# 26_-_PWR_PMIC.net
KiCad netlist of a schematic drawn in Altium Designer
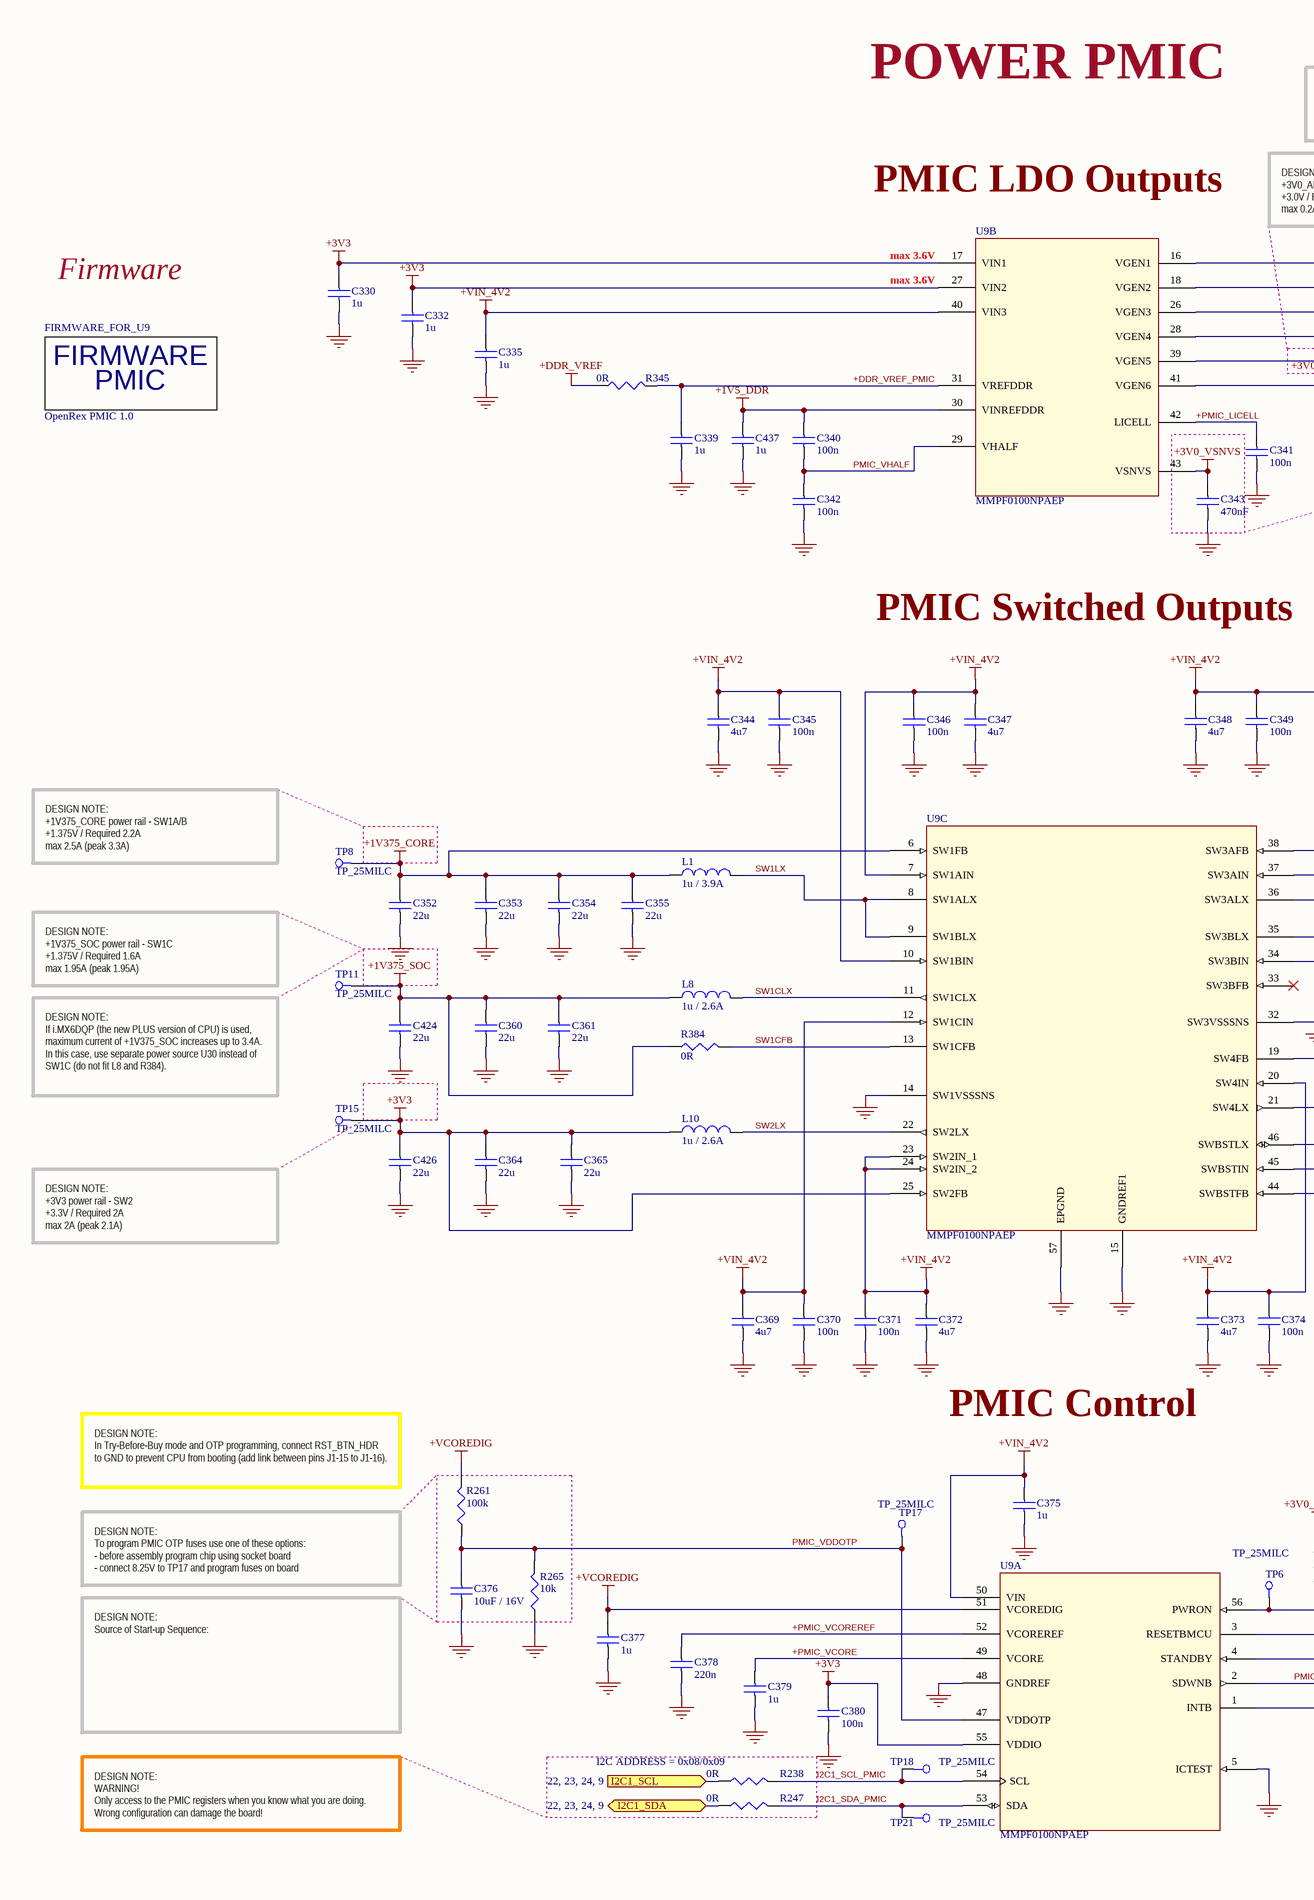
[diagram p0: [26] - PWR PMIC.SchDoc, left]
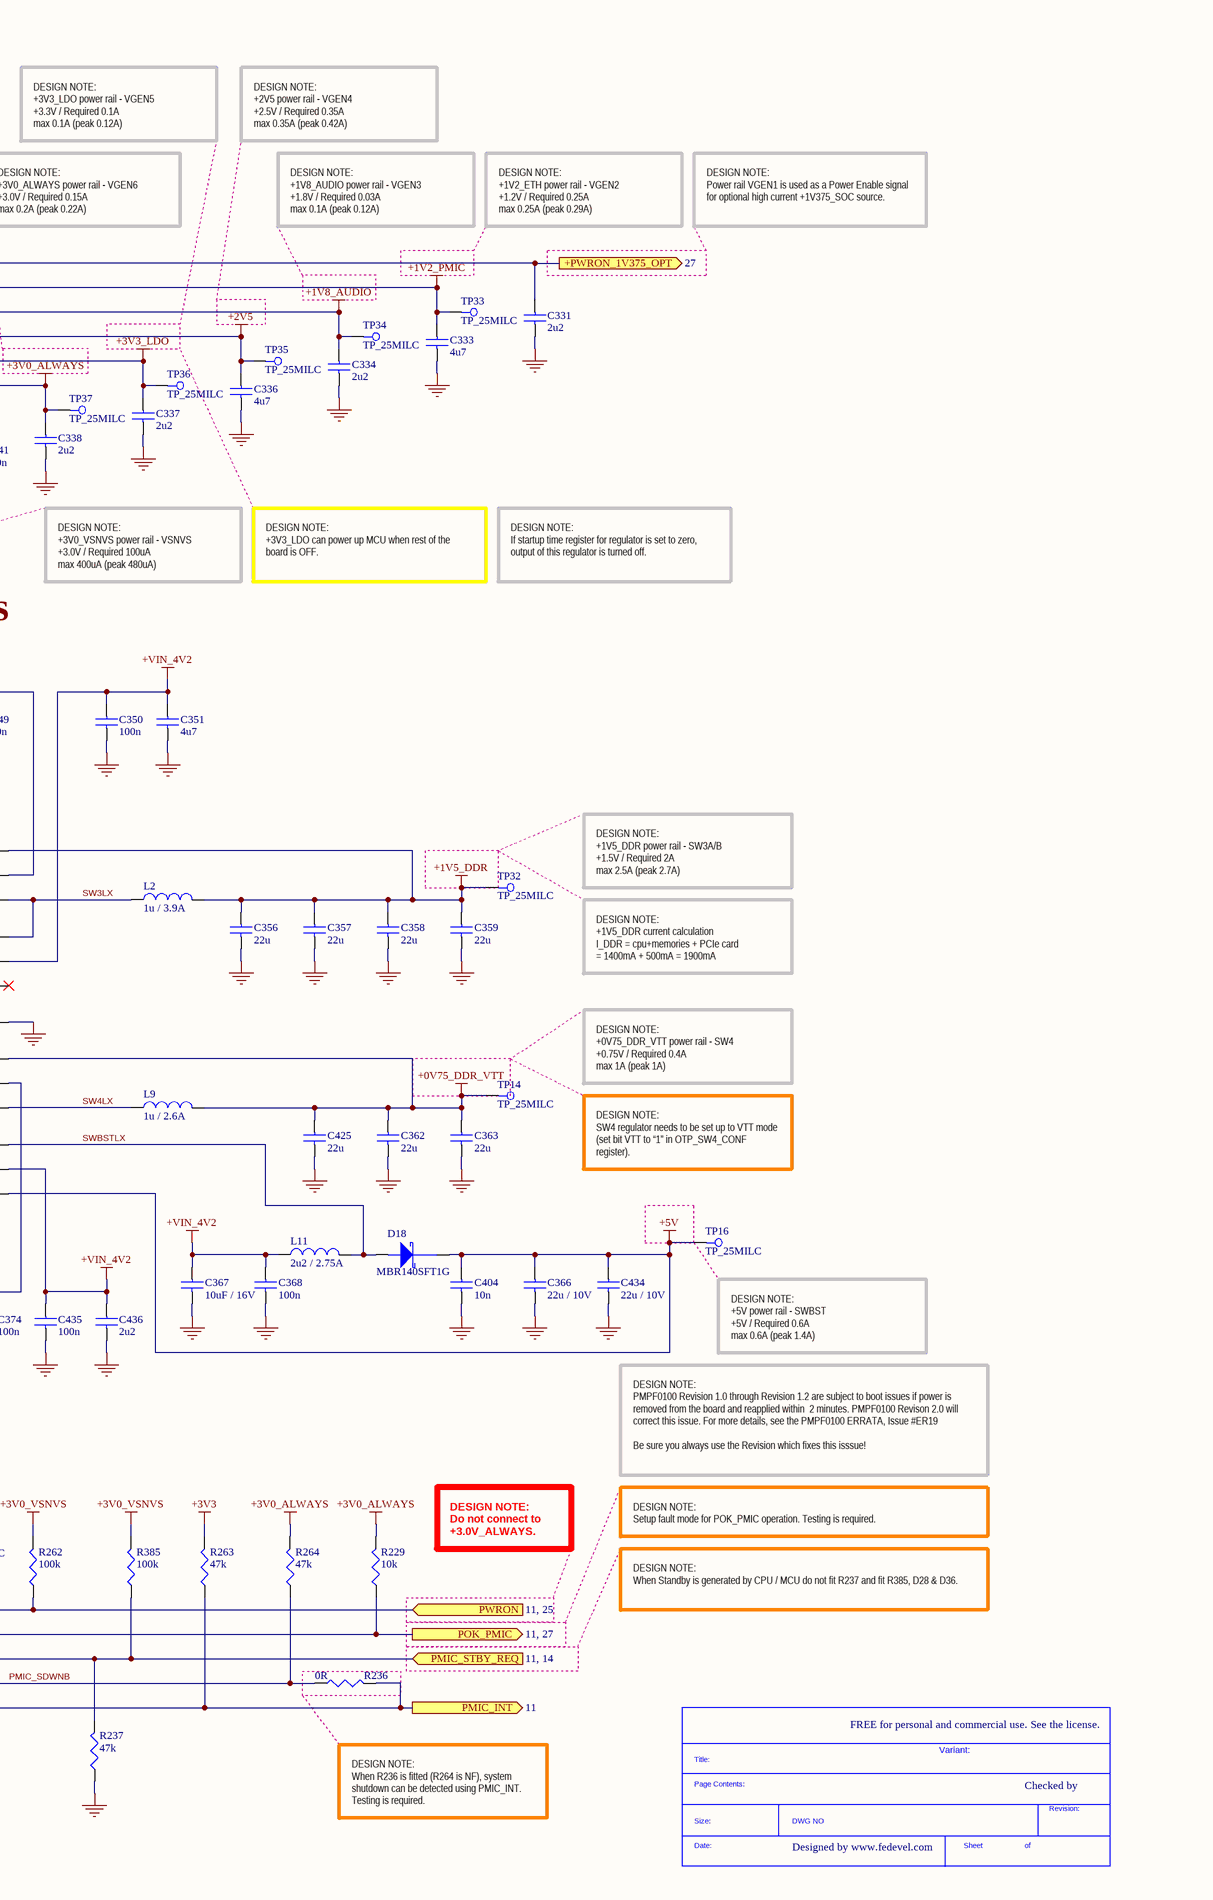
[diagram p1: [26] - PWR PMIC.SchDoc, right]

(export (version "E")
  (design (tool "Eeschema 10.0.6"))
  (components
    (comp (ref "C330")
      (value "1u")
      (footprint "C0402")
      (description "CAP CER 1.0UF 16V X5R 0402")
      (fields
        (field (name "MANUFACTURER") "TDK Corporation")
        (field (name "MANUFACTURER PART NUMBER") "C1005X5R1C105K")
      )
      (libsource (lib "Integrated_Library_FEDEVEL_APR_2015") (part "C1005X5R1C105K"))
    )
    (comp (ref "C331")
      (value "2u2")
      (footprint "C0402")
      (description "CAP CER 2.2UF 10V 10% X5R 0402")
      (fields
        (field (name "MANUFACTURER") "TDK Corporation")
        (field (name "MANUFACTURER PART NUMBER") "C1005X5R1A225K")
      )
      (libsource (lib "Integrated_Library_FEDEVEL_APR_2015") (part "C1005X5R1A225K"))
    )
    (comp (ref "C332")
      (value "1u")
      (footprint "C0402")
      (description "CAP CER 1.0UF 16V X5R 0402")
      (fields
        (field (name "MANUFACTURER") "TDK Corporation")
        (field (name "MANUFACTURER PART NUMBER") "C1005X5R1C105K")
      )
      (libsource (lib "Integrated_Library_FEDEVEL_APR_2015") (part "C1005X5R1C105K"))
    )
    (comp (ref "C333")
      (value "4u7")
      (footprint "C0402")
      (description "CAP CER 4.7UF 10V 20% X5R 0402")
      (fields
        (field (name "MANUFACTURER") "TDK Corporation")
        (field (name "MANUFACTURER PART NUMBER") "C1005X5R1A475M")
      )
      (libsource (lib "Integrated_Library_FEDEVEL_APR_2015") (part "C1005X5R1A475M"))
    )
    (comp (ref "C334")
      (value "2u2")
      (footprint "C0402")
      (description "CAP CER 2.2UF 10V 10% X5R 0402")
      (fields
        (field (name "MANUFACTURER") "TDK Corporation")
        (field (name "MANUFACTURER PART NUMBER") "C1005X5R1A225K")
      )
      (libsource (lib "Integrated_Library_FEDEVEL_APR_2015") (part "C1005X5R1A225K"))
    )
    (comp (ref "C335")
      (value "1u")
      (footprint "C0402")
      (description "CAP CER 1.0UF 16V X5R 0402")
      (fields
        (field (name "MANUFACTURER") "TDK Corporation")
        (field (name "MANUFACTURER PART NUMBER") "C1005X5R1C105K")
      )
      (libsource (lib "Integrated_Library_FEDEVEL_APR_2015") (part "C1005X5R1C105K"))
    )
    (comp (ref "C336")
      (value "4u7")
      (footprint "C0402")
      (description "CAP CER 4.7UF 10V 20% X5R 0402")
      (fields
        (field (name "MANUFACTURER") "TDK Corporation")
        (field (name "MANUFACTURER PART NUMBER") "C1005X5R1A475M")
      )
      (libsource (lib "Integrated_Library_FEDEVEL_APR_2015") (part "C1005X5R1A475M"))
    )
    (comp (ref "C337")
      (value "2u2")
      (footprint "C0402")
      (description "CAP CER 2.2UF 10V 10% X5R 0402")
      (fields
        (field (name "MANUFACTURER") "TDK Corporation")
        (field (name "MANUFACTURER PART NUMBER") "C1005X5R1A225K")
      )
      (libsource (lib "Integrated_Library_FEDEVEL_APR_2015") (part "C1005X5R1A225K"))
    )
    (comp (ref "C338")
      (value "2u2")
      (footprint "C0402")
      (description "CAP CER 2.2UF 10V 10% X5R 0402")
      (fields
        (field (name "MANUFACTURER") "TDK Corporation")
        (field (name "MANUFACTURER PART NUMBER") "C1005X5R1A225K")
      )
      (libsource (lib "Integrated_Library_FEDEVEL_APR_2015") (part "C1005X5R1A225K"))
    )
    (comp (ref "C339")
      (value "1u")
      (footprint "C0402")
      (description "CAP CER 1.0UF 16V X5R 0402")
      (fields
        (field (name "MANUFACTURER") "TDK Corporation")
        (field (name "MANUFACTURER PART NUMBER") "C1005X5R1C105K")
      )
      (libsource (lib "Integrated_Library_FEDEVEL_APR_2015") (part "C1005X5R1C105K"))
    )
    (comp (ref "C340")
      (value "100n")
      (footprint "C0402")
      (description "CAP CER .10UF 50V X5R 10% 0402")
      (fields
        (field (name "MANUFACTURER") "TDK Corporation")
        (field (name "MANUFACTURER PART NUMBER") "C1005X5R1H104K")
      )
      (libsource (lib "Integrated_Library_FEDEVEL_APR_2015") (part "C1005X5R1H104K"))
    )
    (comp (ref "C341")
      (value "100n")
      (footprint "C0402")
      (description "CAP CER .10UF 50V X5R 10% 0402")
      (fields
        (field (name "MANUFACTURER") "TDK Corporation")
        (field (name "MANUFACTURER PART NUMBER") "C1005X5R1H104K")
      )
      (libsource (lib "Integrated_Library_FEDEVEL_APR_2015") (part "C1005X5R1H104K"))
    )
    (comp (ref "C342")
      (value "100n")
      (footprint "C0402")
      (description "CAP CER .10UF 50V X5R 10% 0402")
      (fields
        (field (name "MANUFACTURER") "TDK Corporation")
        (field (name "MANUFACTURER PART NUMBER") "C1005X5R1H104K")
      )
      (libsource (lib "Integrated_Library_FEDEVEL_APR_2015") (part "C1005X5R1H104K"))
    )
    (comp (ref "C343")
      (value "470nF")
      (footprint "C0402")
      (description "CAP CER .47UF 16V X5R 0402")
      (fields
        (field (name "MANUFACTURER") "TDK Corporation")
        (field (name "MANUFACTURER PART NUMBER") "C1005X5R1C474K")
      )
      (libsource (lib "Integrated_Library_FEDEVEL_APR_2015") (part "C1005X5R1C474K"))
    )
    (comp (ref "C344")
      (value "4u7")
      (footprint "C0402")
      (description "CAP CER 4.7UF 10V 20% X5R 0402")
      (fields
        (field (name "MANUFACTURER") "TDK Corporation")
        (field (name "MANUFACTURER PART NUMBER") "C1005X5R1A475M")
      )
      (libsource (lib "Integrated_Library_FEDEVEL_APR_2015") (part "C1005X5R1A475M"))
    )
    (comp (ref "C345")
      (value "100n")
      (footprint "C0402")
      (description "CAP CER .10UF 50V X5R 10% 0402")
      (fields
        (field (name "MANUFACTURER") "TDK Corporation")
        (field (name "MANUFACTURER PART NUMBER") "C1005X5R1H104K")
      )
      (libsource (lib "Integrated_Library_FEDEVEL_APR_2015") (part "C1005X5R1H104K"))
    )
    (comp (ref "C346")
      (value "100n")
      (footprint "C0402")
      (description "CAP CER .10UF 50V X5R 10% 0402")
      (fields
        (field (name "MANUFACTURER") "TDK Corporation")
        (field (name "MANUFACTURER PART NUMBER") "C1005X5R1H104K")
      )
      (libsource (lib "Integrated_Library_FEDEVEL_APR_2015") (part "C1005X5R1H104K"))
    )
    (comp (ref "C347")
      (value "4u7")
      (footprint "C0402")
      (description "CAP CER 4.7UF 10V 20% X5R 0402")
      (fields
        (field (name "MANUFACTURER") "TDK Corporation")
        (field (name "MANUFACTURER PART NUMBER") "C1005X5R1A475M")
      )
      (libsource (lib "Integrated_Library_FEDEVEL_APR_2015") (part "C1005X5R1A475M"))
    )
    (comp (ref "C348")
      (value "4u7")
      (footprint "C0402")
      (description "CAP CER 4.7UF 10V 20% X5R 0402")
      (fields
        (field (name "MANUFACTURER") "TDK Corporation")
        (field (name "MANUFACTURER PART NUMBER") "C1005X5R1A475M")
      )
      (libsource (lib "Integrated_Library_FEDEVEL_APR_2015") (part "C1005X5R1A475M"))
    )
    (comp (ref "C349")
      (value "100n")
      (footprint "C0402")
      (description "CAP CER .10UF 50V X5R 10% 0402")
      (fields
        (field (name "MANUFACTURER") "TDK Corporation")
        (field (name "MANUFACTURER PART NUMBER") "C1005X5R1H104K")
      )
      (libsource (lib "Integrated_Library_FEDEVEL_APR_2015") (part "C1005X5R1H104K"))
    )
    (comp (ref "C350")
      (value "100n")
      (footprint "C0402")
      (description "CAP CER .10UF 50V X5R 10% 0402")
      (fields
        (field (name "MANUFACTURER") "TDK Corporation")
        (field (name "MANUFACTURER PART NUMBER") "C1005X5R1H104K")
      )
      (libsource (lib "Integrated_Library_FEDEVEL_APR_2015") (part "C1005X5R1H104K"))
    )
    (comp (ref "C351")
      (value "4u7")
      (footprint "C0402")
      (description "CAP CER 4.7UF 10V 20% X5R 0402")
      (fields
        (field (name "MANUFACTURER") "TDK Corporation")
        (field (name "MANUFACTURER PART NUMBER") "C1005X5R1A475M")
      )
      (libsource (lib "Integrated_Library_FEDEVEL_APR_2015") (part "C1005X5R1A475M"))
    )
    (comp (ref "C352")
      (value "22u")
      (footprint "C0603")
      (description "CAP CER 22UF 4V 20% X5R 0603")
      (fields
        (field (name "MANUFACTURER") "Murata Electronics North America")
        (field (name "MANUFACTURER PART NUMBER") "GRM188R60G226MEA0L")
      )
      (libsource (lib "Integrated_Library_FEDEVEL_APR_2015") (part "GRM188R60G226MEA0L"))
    )
    (comp (ref "C353")
      (value "22u")
      (footprint "C0603")
      (description "CAP CER 22UF 4V 20% X5R 0603")
      (fields
        (field (name "MANUFACTURER") "Murata Electronics North America")
        (field (name "MANUFACTURER PART NUMBER") "GRM188R60G226MEA0L")
      )
      (libsource (lib "Integrated_Library_FEDEVEL_APR_2015") (part "GRM188R60G226MEA0L"))
    )
    (comp (ref "C354")
      (value "22u")
      (footprint "C0603")
      (description "CAP CER 22UF 4V 20% X5R 0603")
      (fields
        (field (name "MANUFACTURER") "Murata Electronics North America")
        (field (name "MANUFACTURER PART NUMBER") "GRM188R60G226MEA0L")
      )
      (libsource (lib "Integrated_Library_FEDEVEL_APR_2015") (part "GRM188R60G226MEA0L"))
    )
    (comp (ref "C355")
      (value "22u")
      (footprint "C0603")
      (description "CAP CER 22UF 4V 20% X5R 0603")
      (fields
        (field (name "MANUFACTURER") "Murata Electronics North America")
        (field (name "MANUFACTURER PART NUMBER") "GRM188R60G226MEA0L")
      )
      (libsource (lib "Integrated_Library_FEDEVEL_APR_2015") (part "GRM188R60G226MEA0L"))
    )
    (comp (ref "C356")
      (value "22u")
      (footprint "C0603")
      (description "CAP CER 22UF 4V 20% X5R 0603")
      (fields
        (field (name "MANUFACTURER") "Murata Electronics North America")
        (field (name "MANUFACTURER PART NUMBER") "GRM188R60G226MEA0L")
      )
      (libsource (lib "Integrated_Library_FEDEVEL_APR_2015") (part "GRM188R60G226MEA0L"))
    )
    (comp (ref "C357")
      (value "22u")
      (footprint "C0603")
      (description "CAP CER 22UF 4V 20% X5R 0603")
      (fields
        (field (name "MANUFACTURER") "Murata Electronics North America")
        (field (name "MANUFACTURER PART NUMBER") "GRM188R60G226MEA0L")
      )
      (libsource (lib "Integrated_Library_FEDEVEL_APR_2015") (part "GRM188R60G226MEA0L"))
    )
    (comp (ref "C358")
      (value "22u")
      (footprint "C0603")
      (description "CAP CER 22UF 4V 20% X5R 0603")
      (fields
        (field (name "MANUFACTURER") "Murata Electronics North America")
        (field (name "MANUFACTURER PART NUMBER") "GRM188R60G226MEA0L")
      )
      (libsource (lib "Integrated_Library_FEDEVEL_APR_2015") (part "GRM188R60G226MEA0L"))
    )
    (comp (ref "C359")
      (value "22u")
      (footprint "C0603")
      (description "CAP CER 22UF 4V 20% X5R 0603")
      (fields
        (field (name "MANUFACTURER") "Murata Electronics North America")
        (field (name "MANUFACTURER PART NUMBER") "GRM188R60G226MEA0L")
      )
      (libsource (lib "Integrated_Library_FEDEVEL_APR_2015") (part "GRM188R60G226MEA0L"))
    )
    (comp (ref "C360")
      (value "22u")
      (footprint "C0603")
      (description "CAP CER 22UF 4V 20% X5R 0603")
      (fields
        (field (name "MANUFACTURER") "Murata Electronics North America")
        (field (name "MANUFACTURER PART NUMBER") "GRM188R60G226MEA0L")
      )
      (libsource (lib "Integrated_Library_FEDEVEL_APR_2015") (part "GRM188R60G226MEA0L"))
    )
    (comp (ref "C361")
      (value "22u")
      (footprint "C0603")
      (description "CAP CER 22UF 4V 20% X5R 0603")
      (fields
        (field (name "MANUFACTURER") "Murata Electronics North America")
        (field (name "MANUFACTURER PART NUMBER") "GRM188R60G226MEA0L")
      )
      (libsource (lib "Integrated_Library_FEDEVEL_APR_2015") (part "GRM188R60G226MEA0L"))
    )
    (comp (ref "C362")
      (value "22u")
      (footprint "C0603")
      (description "CAP CER 22UF 4V 20% X5R 0603")
      (fields
        (field (name "MANUFACTURER") "Murata Electronics North America")
        (field (name "MANUFACTURER PART NUMBER") "GRM188R60G226MEA0L")
      )
      (libsource (lib "Integrated_Library_FEDEVEL_APR_2015") (part "GRM188R60G226MEA0L"))
    )
    (comp (ref "C363")
      (value "22u")
      (footprint "C0603")
      (description "CAP CER 22UF 4V 20% X5R 0603")
      (fields
        (field (name "MANUFACTURER") "Murata Electronics North America")
        (field (name "MANUFACTURER PART NUMBER") "GRM188R60G226MEA0L")
      )
      (libsource (lib "Integrated_Library_FEDEVEL_APR_2015") (part "GRM188R60G226MEA0L"))
    )
    (comp (ref "C364")
      (value "22u")
      (footprint "C0603")
      (description "CAP CER 22UF 6.3V 20% X5R 0603")
      (fields
        (field (name "MANUFACTURER") "TDK Corporation")
        (field (name "MANUFACTURER PART NUMBER") "C1608X5R0J226M080AC")
      )
      (libsource (lib "Integrated_Library_FEDEVEL_APR_2015") (part "C1608X5R0J226M080AC"))
    )
    (comp (ref "C365")
      (value "22u")
      (footprint "C0603")
      (description "CAP CER 22UF 6.3V 20% X5R 0603")
      (fields
        (field (name "MANUFACTURER") "TDK Corporation")
        (field (name "MANUFACTURER PART NUMBER") "C1608X5R0J226M080AC")
      )
      (libsource (lib "Integrated_Library_FEDEVEL_APR_2015") (part "C1608X5R0J226M080AC"))
    )
    (comp (ref "C366")
      (value "22u / 10V")
      (footprint "C0603")
      (description "CAP CER 22UF 10V X5R 0603")
      (fields
        (field (name "MANUFACTURER") "TDK Corporation")
        (field (name "MANUFACTURER PART NUMBER") "C1608X5R1A226M080AC")
      )
      (libsource (lib "Integrated_Library_FEDEVEL_APR_2015") (part "C1608X5R1A226M080AC"))
    )
    (comp (ref "C367")
      (value "10uF / 16V")
      (footprint "C0805")
      (description "CAP CER 10UF 16V 20% X5R 0805")
      (fields
        (field (name "MANUFACTURER") "TDK Corporation")
        (field (name "MANUFACTURER PART NUMBER") "C2012X5R1C106M/1.25")
      )
      (libsource (lib "Integrated_Library_FEDEVEL_APR_2015") (part "C2012X5R1C106M"))
    )
    (comp (ref "C368")
      (value "100n")
      (footprint "C0402")
      (description "CAP CER .10UF 50V X5R 10% 0402")
      (fields
        (field (name "MANUFACTURER") "TDK Corporation")
        (field (name "MANUFACTURER PART NUMBER") "C1005X5R1H104K")
      )
      (libsource (lib "Integrated_Library_FEDEVEL_APR_2015") (part "C1005X5R1H104K"))
    )
    (comp (ref "C369")
      (value "4u7")
      (footprint "C0402")
      (description "CAP CER 4.7UF 10V 20% X5R 0402")
      (fields
        (field (name "MANUFACTURER") "TDK Corporation")
        (field (name "MANUFACTURER PART NUMBER") "C1005X5R1A475M")
      )
      (libsource (lib "Integrated_Library_FEDEVEL_APR_2015") (part "C1005X5R1A475M"))
    )
    (comp (ref "C370")
      (value "100n")
      (footprint "C0402")
      (description "CAP CER .10UF 50V X5R 10% 0402")
      (fields
        (field (name "MANUFACTURER") "TDK Corporation")
        (field (name "MANUFACTURER PART NUMBER") "C1005X5R1H104K")
      )
      (libsource (lib "Integrated_Library_FEDEVEL_APR_2015") (part "C1005X5R1H104K"))
    )
    (comp (ref "C371")
      (value "100n")
      (footprint "C0402")
      (description "CAP CER .10UF 50V X5R 10% 0402")
      (fields
        (field (name "MANUFACTURER") "TDK Corporation")
        (field (name "MANUFACTURER PART NUMBER") "C1005X5R1H104K")
      )
      (libsource (lib "Integrated_Library_FEDEVEL_APR_2015") (part "C1005X5R1H104K"))
    )
    (comp (ref "C372")
      (value "4u7")
      (footprint "C0402")
      (description "CAP CER 4.7UF 10V 20% X5R 0402")
      (fields
        (field (name "MANUFACTURER") "TDK Corporation")
        (field (name "MANUFACTURER PART NUMBER") "C1005X5R1A475M")
      )
      (libsource (lib "Integrated_Library_FEDEVEL_APR_2015") (part "C1005X5R1A475M"))
    )
    (comp (ref "C373")
      (value "4u7")
      (footprint "C0402")
      (description "CAP CER 4.7UF 10V 20% X5R 0402")
      (fields
        (field (name "MANUFACTURER") "TDK Corporation")
        (field (name "MANUFACTURER PART NUMBER") "C1005X5R1A475M")
      )
      (libsource (lib "Integrated_Library_FEDEVEL_APR_2015") (part "C1005X5R1A475M"))
    )
    (comp (ref "C374")
      (value "100n")
      (footprint "C0402")
      (description "CAP CER .10UF 50V X5R 10% 0402")
      (fields
        (field (name "MANUFACTURER") "TDK Corporation")
        (field (name "MANUFACTURER PART NUMBER") "C1005X5R1H104K")
      )
      (libsource (lib "Integrated_Library_FEDEVEL_APR_2015") (part "C1005X5R1H104K"))
    )
    (comp (ref "C375")
      (value "1u")
      (footprint "C0402")
      (description "CAP CER 1.0UF 16V X5R 0402")
      (fields
        (field (name "MANUFACTURER") "TDK Corporation")
        (field (name "MANUFACTURER PART NUMBER") "C1005X5R1C105K")
      )
      (libsource (lib "Integrated_Library_FEDEVEL_APR_2015") (part "C1005X5R1C105K"))
    )
    (comp (ref "C376")
      (value "10uF / 16V")
      (footprint "C0805")
      (description "CAP CER 10UF 16V 20% X5R 0805")
      (fields
        (field (name "MANUFACTURER") "TDK Corporation")
        (field (name "MANUFACTURER PART NUMBER") "C2012X5R1C106M/1.25")
      )
      (libsource (lib "Integrated_Library_FEDEVEL_APR_2015") (part "C2012X5R1C106M"))
    )
    (comp (ref "C377")
      (value "1u")
      (footprint "C0402")
      (description "CAP CER 1.0UF 16V X5R 0402")
      (fields
        (field (name "MANUFACTURER") "TDK Corporation")
        (field (name "MANUFACTURER PART NUMBER") "C1005X5R1C105K")
      )
      (libsource (lib "Integrated_Library_FEDEVEL_APR_2015") (part "C1005X5R1C105K"))
    )
    (comp (ref "C378")
      (value "220n")
      (footprint "C0402")
      (description "CAP CER .22UF 25V X5R 20% 0402")
      (fields
        (field (name "MANUFACTURER") "TDK Corporation")
        (field (name "MANUFACTURER PART NUMBER") "C1005X5R1E224M")
      )
      (libsource (lib "Integrated_Library_FEDEVEL_APR_2015") (part "C1005X5R1E224M"))
    )
    (comp (ref "C379")
      (value "1u")
      (footprint "C0402")
      (description "CAP CER 1.0UF 16V X5R 0402")
      (fields
        (field (name "MANUFACTURER") "TDK Corporation")
        (field (name "MANUFACTURER PART NUMBER") "C1005X5R1C105K")
      )
      (libsource (lib "Integrated_Library_FEDEVEL_APR_2015") (part "C1005X5R1C105K"))
    )
    (comp (ref "C380")
      (value "100n")
      (footprint "C0402")
      (description "CAP CER .10UF 50V X5R 10% 0402")
      (fields
        (field (name "MANUFACTURER") "TDK Corporation")
        (field (name "MANUFACTURER PART NUMBER") "C1005X5R1H104K")
      )
      (libsource (lib "Integrated_Library_FEDEVEL_APR_2015") (part "C1005X5R1H104K"))
    )
    (comp (ref "C404")
      (value "10n")
      (footprint "C0402")
      (description "CAP CER 10000PF 50V 10% X7R 0402")
      (fields
        (field (name "MANUFACTURER") "TDK Corporation")
        (field (name "MANUFACTURER PART NUMBER") "C1005X7R1H103K")
      )
      (libsource (lib "Integrated_Library_FEDEVEL_APR_2015") (part "C1005X7R1H103K"))
    )
    (comp (ref "C424")
      (value "22u")
      (footprint "C0603")
      (description "CAP CER 22UF 4V 20% X5R 0603")
      (fields
        (field (name "MANUFACTURER") "Murata Electronics North America")
        (field (name "MANUFACTURER PART NUMBER") "GRM188R60G226MEA0L")
      )
      (libsource (lib "Integrated_Library_FEDEVEL_APR_2015") (part "GRM188R60G226MEA0L"))
    )
    (comp (ref "C425")
      (value "22u")
      (footprint "C0603")
      (description "CAP CER 22UF 4V 20% X5R 0603")
      (fields
        (field (name "MANUFACTURER") "Murata Electronics North America")
        (field (name "MANUFACTURER PART NUMBER") "GRM188R60G226MEA0L")
      )
      (libsource (lib "Integrated_Library_FEDEVEL_APR_2015") (part "GRM188R60G226MEA0L"))
    )
    (comp (ref "C426")
      (value "22u")
      (footprint "C0603")
      (description "CAP CER 22UF 6.3V 20% X5R 0603")
      (fields
        (field (name "MANUFACTURER") "TDK Corporation")
        (field (name "MANUFACTURER PART NUMBER") "C1608X5R0J226M080AC")
      )
      (libsource (lib "Integrated_Library_FEDEVEL_APR_2015") (part "C1608X5R0J226M080AC"))
    )
    (comp (ref "C434")
      (value "22u / 10V")
      (footprint "C0603")
      (description "CAP CER 22UF 10V X5R 0603")
      (fields
        (field (name "MANUFACTURER") "TDK Corporation")
        (field (name "MANUFACTURER PART NUMBER") "C1608X5R1A226M080AC")
      )
      (libsource (lib "Integrated_Library_FEDEVEL_APR_2015") (part "C1608X5R1A226M080AC"))
    )
    (comp (ref "C435")
      (value "100n")
      (footprint "C0402")
      (description "CAP CER .10UF 50V X5R 10% 0402")
      (fields
        (field (name "MANUFACTURER") "TDK Corporation")
        (field (name "MANUFACTURER PART NUMBER") "C1005X5R1H104K")
      )
      (libsource (lib "Integrated_Library_FEDEVEL_APR_2015") (part "C1005X5R1H104K"))
    )
    (comp (ref "C436")
      (value "2u2")
      (footprint "C0402")
      (description "CAP CER 2.2UF 10V 10% X5R 0402")
      (fields
        (field (name "MANUFACTURER") "TDK Corporation")
        (field (name "MANUFACTURER PART NUMBER") "C1005X5R1A225K")
      )
      (libsource (lib "Integrated_Library_FEDEVEL_APR_2015") (part "C1005X5R1A225K"))
    )
    (comp (ref "C437")
      (value "1u")
      (footprint "C0402")
      (description "CAP CER 1.0UF 16V X5R 0402")
      (fields
        (field (name "MANUFACTURER") "TDK Corporation")
        (field (name "MANUFACTURER PART NUMBER") "C1005X5R1C105K")
      )
      (libsource (lib "Integrated_Library_FEDEVEL_APR_2015") (part "C1005X5R1C105K"))
    )
    (comp (ref "D18")
      (value "MBR140SFT1G")
      (footprint "SOD-123FL")
      (description "DIODE SCHOTTKY 40V 1A SOD123L")
      (fields (field (name "MANUFACTURER") "ON Semiconductor"))
      (libsource (lib "Integrated_Library_FEDEVEL_APR_2015") (part "MBR140SFT1G"))
    )
    (comp (ref "FIRMWARE_FOR_U9")
      (value "OpenRex PMIC 1.0")
      (libsource (lib "Integrated_Library_FEDEVEL_APR_2015") (part "FIRMWARE_OpenRex_PMIC_1.0"))
    )
    (comp (ref "L1")
      (value "1u / 3.9A")
      (footprint "IHLP_118MILX144MIL")
      (description "FIXED IND 1UH 3.9A 33 MOHM SMD")
      (fields
        (field (name "MANUFACTURER") "Vishay Dale")
        (field (name "MANUFACTURER PART NUMBER") "IHLP1212AEER1R0M11")
      )
      (libsource (lib "") (part "IHLP1212AEER1R0M11_1"))
    )
    (comp (ref "L2")
      (value "1u / 3.9A")
      (footprint "IHLP_118MILX144MIL")
      (description "FIXED IND 1UH 3.9A 33 MOHM SMD")
      (fields
        (field (name "MANUFACTURER") "Vishay Dale")
        (field (name "MANUFACTURER PART NUMBER") "IHLP1212AEER1R0M11")
      )
      (libsource (lib "Integrated_Library_FEDEVEL_APR_2015") (part "IHLP1212AEER1R0M11"))
    )
    (comp (ref "L8")
      (value "1u / 2.6A")
      (footprint "IFSC_79MILX98MIL")
      (description "FIXED IND 1UH 2.6A 43 MOHM SMD")
      (fields
        (field (name "MANUFACTURER") "Vishay Dale")
        (field (name "MANUFACTURER PART NUMBER") "IFSC1008ABER1R0M01")
      )
      (libsource (lib "Integrated_Library_FEDEVEL_APR_2015") (part "IFSC1008ABER1R0M01"))
    )
    (comp (ref "L9")
      (value "1u / 2.6A")
      (footprint "IFSC_79MILX98MIL")
      (description "FIXED IND 1UH 2.6A 43 MOHM SMD")
      (fields
        (field (name "MANUFACTURER") "Vishay Dale")
        (field (name "MANUFACTURER PART NUMBER") "IFSC1008ABER1R0M01")
      )
      (libsource (lib "Integrated_Library_FEDEVEL_APR_2015") (part "IFSC1008ABER1R0M01"))
    )
    (comp (ref "L10")
      (value "1u / 2.6A")
      (footprint "IFSC_79MILX98MIL")
      (description "FIXED IND 1UH 2.6A 43 MOHM SMD")
      (fields
        (field (name "MANUFACTURER") "Vishay Dale")
        (field (name "MANUFACTURER PART NUMBER") "IFSC1008ABER1R0M01")
      )
      (libsource (lib "") (part "IFSC1008ABER1R0M01_1"))
    )
    (comp (ref "L11")
      (value "2u2 / 2.75A")
      (footprint "IHLP_160MILX175MIL")
      (description "FIXED IND 2.2UH 2.75A 83.5 MOHM")
      (fields
        (field (name "MANUFACTURER") "Vishay Dale")
        (field (name "MANUFACTURER PART NUMBER") "IHLP1616ABER2R2M11")
      )
      (libsource (lib "Integrated_Library_FEDEVEL_APR_2015") (part "IHLP1616ABER2R2M11"))
    )
    (comp (ref "R229")
      (value "10k")
      (footprint "R0402")
      (description "RES 10.0K OHM 1/16W 1% 0402 SMD")
      (fields
        (field (name "MANUFACTURER") "Yageo")
        (field (name "MANUFACTURER PART NUMBER") "RC0402FR-0710KL")
      )
      (libsource (lib "Integrated_Library_FEDEVEL_APR_2015") (part "RC0402FR-0710KL"))
    )
    (comp (ref "R236")
      (value "0R")
      (footprint "R0402")
      (description "RES 0.0 OHM 1/16W 0402 SMD")
      (fields
        (field (name "MANUFACTURER") "Yageo")
        (field (name "MANUFACTURER PART NUMBER") "RC0402JR-070RL")
      )
      (libsource (lib "Integrated_Library_FEDEVEL_APR_2015") (part "RC0402JR-070RL"))
    )
    (comp (ref "R237")
      (value "47k")
      (footprint "R0402")
      (description "RES 47.0K OHM 1/16W 1% 0402 SMD")
      (fields
        (field (name "MANUFACTURER") "Yageo")
        (field (name "MANUFACTURER PART NUMBER") "RC0402FR-0747KL")
      )
      (libsource (lib "Integrated_Library_FEDEVEL_APR_2015") (part "RC0402FR-0747KL"))
    )
    (comp (ref "R238")
      (value "0R")
      (footprint "R0402")
      (description "RES 0.0 OHM 1/16W 0402 SMD")
      (fields
        (field (name "MANUFACTURER") "Yageo")
        (field (name "MANUFACTURER PART NUMBER") "RC0402JR-070RL")
      )
      (libsource (lib "Integrated_Library_FEDEVEL_APR_2015") (part "RC0402JR-070RL"))
    )
    (comp (ref "R247")
      (value "0R")
      (footprint "R0402")
      (description "RES 0.0 OHM 1/16W 0402 SMD")
      (fields
        (field (name "MANUFACTURER") "Yageo")
        (field (name "MANUFACTURER PART NUMBER") "RC0402JR-070RL")
      )
      (libsource (lib "Integrated_Library_FEDEVEL_APR_2015") (part "RC0402JR-070RL"))
    )
    (comp (ref "R261")
      (value "100k")
      (footprint "R0402")
      (description "RES 100K OHM 1/16W 1% 0402 SMD")
      (fields
        (field (name "MANUFACTURER") "Stackpole Electronics Inc")
        (field (name "MANUFACTURER PART NUMBER") "RMCF0402FT100K")
      )
      (libsource (lib "Integrated_Library_FEDEVEL_APR_2015") (part "RMCF0402FT100K"))
    )
    (comp (ref "R262")
      (value "100k")
      (footprint "R0402")
      (description "RES 100K OHM 1/16W 1% 0402 SMD")
      (fields
        (field (name "MANUFACTURER") "Stackpole Electronics Inc")
        (field (name "MANUFACTURER PART NUMBER") "RMCF0402FT100K")
      )
      (libsource (lib "Integrated_Library_FEDEVEL_APR_2015") (part "RMCF0402FT100K"))
    )
    (comp (ref "R263")
      (value "47k")
      (footprint "R0402")
      (description "RES 47.0K OHM 1/16W 1% 0402 SMD")
      (fields
        (field (name "MANUFACTURER") "Yageo")
        (field (name "MANUFACTURER PART NUMBER") "RC0402FR-0747KL")
      )
      (libsource (lib "Integrated_Library_FEDEVEL_APR_2015") (part "RC0402FR-0747KL"))
    )
    (comp (ref "R264")
      (value "47k")
      (footprint "R0402")
      (description "RES 47.0K OHM 1/16W 1% 0402 SMD")
      (fields
        (field (name "MANUFACTURER") "Yageo")
        (field (name "MANUFACTURER PART NUMBER") "RC0402FR-0747KL")
      )
      (libsource (lib "Integrated_Library_FEDEVEL_APR_2015") (part "RC0402FR-0747KL"))
    )
    (comp (ref "R265")
      (value "10k")
      (footprint "R0402")
      (description "RES 10.0K OHM 1/16W 1% 0402 SMD")
      (fields
        (field (name "MANUFACTURER") "Yageo")
        (field (name "MANUFACTURER PART NUMBER") "RC0402FR-0710KL")
      )
      (libsource (lib "Integrated_Library_FEDEVEL_APR_2015") (part "RC0402FR-0710KL"))
    )
    (comp (ref "R345")
      (value "0R")
      (footprint "R0402")
      (description "RES 0.0 OHM 1/16W 0402 SMD")
      (fields
        (field (name "MANUFACTURER") "Yageo")
        (field (name "MANUFACTURER PART NUMBER") "RC0402JR-070RL")
      )
      (libsource (lib "Integrated_Library_FEDEVEL_APR_2015") (part "RC0402JR-070RL"))
    )
    (comp (ref "R384")
      (value "0R")
      (footprint "R0402")
      (description "RES 0.0 OHM 1/16W 0402 SMD")
      (fields
        (field (name "MANUFACTURER") "Yageo")
        (field (name "MANUFACTURER PART NUMBER") "RC0402JR-070RL")
      )
      (libsource (lib "Integrated_Library_FEDEVEL_APR_2015") (part "RC0402JR-070RL"))
    )
    (comp (ref "R385")
      (value "100k")
      (footprint "R0402")
      (description "RES 100K OHM 1/16W 1% 0402 SMD")
      (fields
        (field (name "MANUFACTURER") "Stackpole Electronics Inc")
        (field (name "MANUFACTURER PART NUMBER") "RMCF0402FT100K")
      )
      (libsource (lib "Integrated_Library_FEDEVEL_APR_2015") (part "RMCF0402FT100K"))
    )
    (comp (ref "TP6")
      (value "TP_25MILC")
      (footprint "TP_25C")
      (description "Test Point 25mil")
      (libsource (lib "Integrated_Library_FEDEVEL_APR_2015") (part "TP_25MILC"))
    )
    (comp (ref "TP8")
      (value "TP_25MILC")
      (footprint "TP_25C")
      (description "Test Point 25mil")
      (libsource (lib "Integrated_Library_FEDEVEL_APR_2015") (part "TP_25MILC"))
    )
    (comp (ref "TP11")
      (value "TP_25MILC")
      (footprint "TP_25C")
      (description "Test Point 25mil")
      (libsource (lib "Integrated_Library_FEDEVEL_APR_2015") (part "TP_25MILC"))
    )
    (comp (ref "TP14")
      (value "TP_25MILC")
      (footprint "TP_25C")
      (description "Test Point 25mil")
      (libsource (lib "Integrated_Library_FEDEVEL_APR_2015") (part "TP_25MILC"))
    )
    (comp (ref "TP15")
      (value "TP_25MILC")
      (footprint "TP_25C")
      (description "Test Point 25mil")
      (libsource (lib "Integrated_Library_FEDEVEL_APR_2015") (part "TP_25MILC"))
    )
    (comp (ref "TP16")
      (value "TP_25MILC")
      (footprint "TP_25C")
      (description "Test Point 25mil")
      (libsource (lib "Integrated_Library_FEDEVEL_APR_2015") (part "TP_25MILC"))
    )
    (comp (ref "TP17")
      (value "TP_25MILC")
      (footprint "TP_25C")
      (description "Test Point 25mil")
      (libsource (lib "Integrated_Library_FEDEVEL_APR_2015") (part "TP_25MILC"))
    )
    (comp (ref "TP18")
      (value "TP_25MILC")
      (footprint "TP_25C")
      (description "Test Point 25mil")
      (libsource (lib "Integrated_Library_FEDEVEL_APR_2015") (part "TP_25MILC"))
    )
    (comp (ref "TP21")
      (value "TP_25MILC")
      (footprint "TP_25C")
      (description "Test Point 25mil")
      (libsource (lib "Integrated_Library_FEDEVEL_APR_2015") (part "TP_25MILC"))
    )
    (comp (ref "TP32")
      (value "TP_25MILC")
      (footprint "TP_25C")
      (description "Test Point 25mil")
      (libsource (lib "Integrated_Library_FEDEVEL_APR_2015") (part "TP_25MILC"))
    )
    (comp (ref "TP33")
      (value "TP_25MILC")
      (footprint "TP_25C")
      (description "Test Point 25mil")
      (libsource (lib "Integrated_Library_FEDEVEL_APR_2015") (part "TP_25MILC"))
    )
    (comp (ref "TP34")
      (value "TP_25MILC")
      (footprint "TP_25C")
      (description "Test Point 25mil")
      (libsource (lib "Integrated_Library_FEDEVEL_APR_2015") (part "TP_25MILC"))
    )
    (comp (ref "TP35")
      (value "TP_25MILC")
      (footprint "TP_25C")
      (description "Test Point 25mil")
      (libsource (lib "Integrated_Library_FEDEVEL_APR_2015") (part "TP_25MILC"))
    )
    (comp (ref "TP36")
      (value "TP_25MILC")
      (footprint "TP_25C")
      (description "Test Point 25mil")
      (libsource (lib "Integrated_Library_FEDEVEL_APR_2015") (part "TP_25MILC"))
    )
    (comp (ref "TP37")
      (value "TP_25MILC")
      (footprint "TP_25C")
      (description "Test Point 25mil")
      (libsource (lib "Integrated_Library_FEDEVEL_APR_2015") (part "TP_25MILC"))
    )
    (comp (ref "U9")
      (value "MMPF0100NPAEP")
      (footprint "56-VFQFN EP")
      (description "IC PWR MGMT I.MX6 56QFN")
      (fields (field (name "MANUFACTURER") "Freescale Semiconductor"))
      (libsource (lib "Integrated_Library_FEDEVEL_APR_2015") (part "MMPF0100NPAEP"))
    )
  )
  (nets
    (net (code "1") (name "+0V75_DDR_VTT") (class "Default")
      (node (ref "C362") (pin "1") (pinfunction "1_1") (pintype "passive"))
      (node (ref "C363") (pin "1") (pinfunction "1_1") (pintype "passive"))
      (node (ref "C425") (pin "1") (pinfunction "1_1") (pintype "passive"))
      (node (ref "L9") (pin "2") (pinfunction "2_2") (pintype "passive"))
      (node (ref "TP14") (pin "1") (pinfunction "1_1") (pintype "passive"))
      (node (ref "U9") (pin "19") (pinfunction "SW4FB_19") (pintype "passive"))
    )
    (net (code "2") (name "+1V2_PMIC") (class "Default")
      (node (ref "C333") (pin "1") (pinfunction "1_1") (pintype "passive"))
      (node (ref "TP33") (pin "1") (pinfunction "1_1") (pintype "passive"))
      (node (ref "U9") (pin "18") (pinfunction "VGEN2_18") (pintype "power_in"))
    )
    (net (code "3") (name "+1V5_DDR") (class "Default")
      (node (ref "C340") (pin "1") (pinfunction "1_1") (pintype "passive"))
      (node (ref "C356") (pin "1") (pinfunction "1_1") (pintype "passive"))
      (node (ref "C357") (pin "1") (pinfunction "1_1") (pintype "passive"))
      (node (ref "C358") (pin "1") (pinfunction "1_1") (pintype "passive"))
      (node (ref "C359") (pin "1") (pinfunction "1_1") (pintype "passive"))
      (node (ref "C437") (pin "1") (pinfunction "1_1") (pintype "passive"))
      (node (ref "L2") (pin "2") (pinfunction "2_2") (pintype "passive"))
      (node (ref "TP32") (pin "1") (pinfunction "1_1") (pintype "passive"))
      (node (ref "U9") (pin "30") (pinfunction "VINREFDDR_30") (pintype "power_in"))
      (node (ref "U9") (pin "38") (pinfunction "SW3AFB_38") (pintype "input"))
    )
    (net (code "4") (name "+1V8_AUDIO") (class "Default")
      (node (ref "C334") (pin "1") (pinfunction "1_1") (pintype "passive"))
      (node (ref "TP34") (pin "1") (pinfunction "1_1") (pintype "passive"))
      (node (ref "U9") (pin "26") (pinfunction "VGEN3_26") (pintype "power_in"))
    )
    (net (code "5") (name "+1V375_CORE") (class "Default")
      (node (ref "C352") (pin "1") (pinfunction "1_1") (pintype "passive"))
      (node (ref "C353") (pin "1") (pinfunction "1_1") (pintype "passive"))
      (node (ref "C354") (pin "1") (pinfunction "1_1") (pintype "passive"))
      (node (ref "C355") (pin "1") (pinfunction "1_1") (pintype "passive"))
      (node (ref "L1") (pin "2") (pinfunction "2_2") (pintype "passive"))
      (node (ref "TP8") (pin "1") (pinfunction "1_1") (pintype "passive"))
      (node (ref "U9") (pin "6") (pinfunction "SW1FB_6") (pintype "input"))
    )
    (net (code "6") (name "+1V375_SOC") (class "Default")
      (node (ref "C360") (pin "1") (pinfunction "1_1") (pintype "passive"))
      (node (ref "C361") (pin "1") (pinfunction "1_1") (pintype "passive"))
      (node (ref "C424") (pin "1") (pinfunction "1_1") (pintype "passive"))
      (node (ref "L8") (pin "1") (pinfunction "1_1") (pintype "passive"))
      (node (ref "R384") (pin "1") (pinfunction "1_1") (pintype "passive"))
      (node (ref "TP11") (pin "1") (pinfunction "1_1") (pintype "passive"))
    )
    (net (code "7") (name "+2V5") (class "Default")
      (node (ref "C336") (pin "1") (pinfunction "1_1") (pintype "passive"))
      (node (ref "TP35") (pin "1") (pinfunction "1_1") (pintype "passive"))
      (node (ref "U9") (pin "28") (pinfunction "VGEN4_28") (pintype "power_in"))
    )
    (net (code "8") (name "+3V0_ALWAYS") (class "Default")
      (node (ref "C338") (pin "1") (pinfunction "1_1") (pintype "passive"))
      (node (ref "R229") (pin "2") (pinfunction "2_2") (pintype "passive"))
      (node (ref "R264") (pin "2") (pinfunction "2_2") (pintype "passive"))
      (node (ref "TP37") (pin "1") (pinfunction "1_1") (pintype "passive"))
      (node (ref "U9") (pin "41") (pinfunction "VGEN6_41") (pintype "power_in"))
    )
    (net (code "9") (name "+3V0_VSNVS") (class "Default")
      (node (ref "C343") (pin "1") (pinfunction "1_1") (pintype "passive"))
      (node (ref "R262") (pin "2") (pinfunction "2_2") (pintype "passive"))
      (node (ref "R385") (pin "2") (pinfunction "2_2") (pintype "passive"))
      (node (ref "U9") (pin "43") (pinfunction "VSNVS_43") (pintype "power_in"))
    )
    (net (code "10") (name "+3V3") (class "Default")
      (node (ref "C330") (pin "1") (pinfunction "1_1") (pintype "passive"))
      (node (ref "C332") (pin "1") (pinfunction "1_1") (pintype "passive"))
      (node (ref "C364") (pin "1") (pinfunction "1_1") (pintype "passive"))
      (node (ref "C365") (pin "1") (pinfunction "1_1") (pintype "passive"))
      (node (ref "C380") (pin "1") (pinfunction "1_1") (pintype "passive"))
      (node (ref "C426") (pin "1") (pinfunction "1_1") (pintype "passive"))
      (node (ref "L10") (pin "2") (pinfunction "2_2") (pintype "passive"))
      (node (ref "R263") (pin "2") (pinfunction "2_2") (pintype "passive"))
      (node (ref "TP15") (pin "1") (pinfunction "1_1") (pintype "passive"))
      (node (ref "U9") (pin "17") (pinfunction "VIN1_17") (pintype "power_in"))
      (node (ref "U9") (pin "25") (pinfunction "SW2FB_25") (pintype "input"))
      (node (ref "U9") (pin "27") (pinfunction "VIN2_27") (pintype "power_in"))
      (node (ref "U9") (pin "55") (pinfunction "VDDIO_55") (pintype "power_in"))
    )
    (net (code "11") (name "+3V3_LDO") (class "Default")
      (node (ref "C337") (pin "1") (pinfunction "1_1") (pintype "passive"))
      (node (ref "TP36") (pin "1") (pinfunction "1_1") (pintype "passive"))
      (node (ref "U9") (pin "39") (pinfunction "VGEN5_39") (pintype "power_in"))
    )
    (net (code "12") (name "+5V") (class "Default")
      (node (ref "C366") (pin "1") (pinfunction "1_1") (pintype "passive"))
      (node (ref "C404") (pin "1") (pinfunction "1_1") (pintype "passive"))
      (node (ref "C434") (pin "1") (pinfunction "1_1") (pintype "passive"))
      (node (ref "D18") (pin "1") (pinfunction "Cathode_1") (pintype "passive"))
      (node (ref "TP16") (pin "1") (pinfunction "1_1") (pintype "passive"))
      (node (ref "U9") (pin "44") (pinfunction "SWBSTFB_44") (pintype "input"))
    )
    (net (code "13") (name "+DDR_VREF") (class "Default")
      (node (ref "R345") (pin "1") (pinfunction "1_1") (pintype "passive"))
    )
    (net (code "14") (name "+VCOREDIG") (class "Default")
      (node (ref "C377") (pin "1") (pinfunction "1_1") (pintype "passive"))
      (node (ref "R261") (pin "2") (pinfunction "2_2") (pintype "passive"))
      (node (ref "U9") (pin "51") (pinfunction "VCOREDIG_51") (pintype "power_in"))
    )
    (net (code "15") (name "+VIN_4V2") (class "Default")
      (node (ref "C335") (pin "1") (pinfunction "1_1") (pintype "passive"))
      (node (ref "C344") (pin "1") (pinfunction "1_1") (pintype "passive"))
      (node (ref "C345") (pin "1") (pinfunction "1_1") (pintype "passive"))
      (node (ref "C346") (pin "1") (pinfunction "1_1") (pintype "passive"))
      (node (ref "C347") (pin "1") (pinfunction "1_1") (pintype "passive"))
      (node (ref "C348") (pin "1") (pinfunction "1_1") (pintype "passive"))
      (node (ref "C349") (pin "1") (pinfunction "1_1") (pintype "passive"))
      (node (ref "C350") (pin "1") (pinfunction "1_1") (pintype "passive"))
      (node (ref "C351") (pin "1") (pinfunction "1_1") (pintype "passive"))
      (node (ref "C367") (pin "1") (pinfunction "1_1") (pintype "passive"))
      (node (ref "C368") (pin "1") (pinfunction "1_1") (pintype "passive"))
      (node (ref "C369") (pin "1") (pinfunction "1_1") (pintype "passive"))
      (node (ref "C370") (pin "1") (pinfunction "1_1") (pintype "passive"))
      (node (ref "C371") (pin "1") (pinfunction "1_1") (pintype "passive"))
      (node (ref "C372") (pin "1") (pinfunction "1_1") (pintype "passive"))
      (node (ref "C373") (pin "1") (pinfunction "1_1") (pintype "passive"))
      (node (ref "C374") (pin "1") (pinfunction "1_1") (pintype "passive"))
      (node (ref "C375") (pin "1") (pinfunction "1_1") (pintype "passive"))
      (node (ref "C435") (pin "1") (pinfunction "1_1") (pintype "passive"))
      (node (ref "C436") (pin "1") (pinfunction "1_1") (pintype "passive"))
      (node (ref "L11") (pin "1") (pinfunction "1_1") (pintype "passive"))
      (node (ref "U9") (pin "10") (pinfunction "SW1BIN_10") (pintype "input"))
      (node (ref "U9") (pin "12") (pinfunction "SW1CIN_12") (pintype "input"))
      (node (ref "U9") (pin "20") (pinfunction "SW4IN_20") (pintype "input"))
      (node (ref "U9") (pin "23") (pinfunction "SW2IN_1_23") (pintype "input"))
      (node (ref "U9") (pin "24") (pinfunction "SW2IN_2_24") (pintype "input"))
      (node (ref "U9") (pin "34") (pinfunction "SW3BIN_34") (pintype "input"))
      (node (ref "U9") (pin "37") (pinfunction "SW3AIN_37") (pintype "input"))
      (node (ref "U9") (pin "40") (pinfunction "VIN3_40") (pintype "power_in"))
      (node (ref "U9") (pin "45") (pinfunction "SWBSTIN_45") (pintype "input"))
      (node (ref "U9") (pin "50") (pinfunction "VIN_50") (pintype "power_in"))
      (node (ref "U9") (pin "7") (pinfunction "SW1AIN_7") (pintype "input"))
    )
    (net (code "16") (name "/+DDR_VREF_PMIC") (class "Default")
      (node (ref "C339") (pin "1") (pinfunction "1_1") (pintype "passive"))
      (node (ref "R345") (pin "2") (pinfunction "2_2") (pintype "passive"))
      (node (ref "U9") (pin "31") (pinfunction "VREFDDR_31") (pintype "power_in"))
    )
    (net (code "17") (name "/+PMIC_LICELL") (class "Default")
      (node (ref "C341") (pin "1") (pinfunction "1_1") (pintype "passive"))
      (node (ref "U9") (pin "42") (pinfunction "LICELL_42") (pintype "power_in"))
    )
    (net (code "18") (name "/+PMIC_VCORE") (class "Default")
      (node (ref "C379") (pin "1") (pinfunction "1_1") (pintype "passive"))
      (node (ref "U9") (pin "49") (pinfunction "VCORE_49") (pintype "power_in"))
    )
    (net (code "19") (name "/+PMIC_VCOREREF") (class "Default")
      (node (ref "C378") (pin "1") (pinfunction "1_1") (pintype "passive"))
      (node (ref "U9") (pin "52") (pinfunction "VCOREREF_52") (pintype "power_in"))
    )
    (net (code "20") (name "/+PWRON_1V375_OPT") (class "Default")
      (node (ref "C331") (pin "1") (pinfunction "1_1") (pintype "passive"))
      (node (ref "U9") (pin "16") (pinfunction "VGEN1_16") (pintype "power_in"))
    )
    (net (code "21") (name "/I2C1_SCL") (class "Default")
      (node (ref "R238") (pin "1") (pinfunction "1_1") (pintype "passive"))
    )
    (net (code "22") (name "/I2C1_SCL_PMIC") (class "Default")
      (node (ref "R238") (pin "2") (pinfunction "2_2") (pintype "passive"))
      (node (ref "TP18") (pin "1") (pinfunction "1_1") (pintype "passive"))
      (node (ref "U9") (pin "54") (pinfunction "SCL_54") (pintype "passive"))
    )
    (net (code "23") (name "/I2C1_SDA") (class "Default")
      (node (ref "R247") (pin "1") (pinfunction "1_1") (pintype "passive"))
    )
    (net (code "24") (name "/I2C1_SDA_PMIC") (class "Default")
      (node (ref "R247") (pin "2") (pinfunction "2_2") (pintype "passive"))
      (node (ref "TP21") (pin "1") (pinfunction "1_1") (pintype "passive"))
      (node (ref "U9") (pin "53") (pinfunction "SDA_53") (pintype "bidirectional"))
    )
    (net (code "25") (name "/PMIC_INT") (class "Default")
      (node (ref "R236") (pin "2") (pinfunction "2_2") (pintype "passive"))
      (node (ref "R263") (pin "1") (pinfunction "1_1") (pintype "passive"))
      (node (ref "U9") (pin "1") (pinfunction "INTB_1") (pintype "passive"))
    )
    (net (code "26") (name "/PMIC_SDWNB") (class "Default")
      (node (ref "R236") (pin "1") (pinfunction "1_1") (pintype "passive"))
      (node (ref "R264") (pin "1") (pinfunction "1_1") (pintype "passive"))
      (node (ref "U9") (pin "2") (pinfunction "SDWNB_2") (pintype "output"))
    )
    (net (code "27") (name "/PMIC_STBY_REQ") (class "Default")
      (node (ref "R237") (pin "2") (pinfunction "2_2") (pintype "passive"))
      (node (ref "R385") (pin "1") (pinfunction "1_1") (pintype "passive"))
      (node (ref "U9") (pin "4") (pinfunction "STANDBY_4") (pintype "input"))
    )
    (net (code "28") (name "/PMIC_VDDOTP") (class "Default")
      (node (ref "C376") (pin "1") (pinfunction "1_1") (pintype "passive"))
      (node (ref "R261") (pin "1") (pinfunction "1_1") (pintype "passive"))
      (node (ref "R265") (pin "2") (pinfunction "2_2") (pintype "passive"))
      (node (ref "TP17") (pin "1") (pinfunction "1_1") (pintype "passive"))
      (node (ref "U9") (pin "47") (pinfunction "VDDOTP_47") (pintype "passive"))
    )
    (net (code "29") (name "/PMIC_VHALF") (class "Default")
      (node (ref "C340") (pin "2") (pinfunction "2_2") (pintype "passive"))
      (node (ref "C342") (pin "1") (pinfunction "1_1") (pintype "passive"))
      (node (ref "U9") (pin "29") (pinfunction "VHALF_29") (pintype "power_in"))
    )
    (net (code "30") (name "/POK_PMIC") (class "Default")
      (node (ref "R229") (pin "1") (pinfunction "1_1") (pintype "passive"))
      (node (ref "U9") (pin "3") (pinfunction "RESETBMCU_3") (pintype "passive"))
    )
    (net (code "31") (name "/PWRON") (class "Default")
      (node (ref "R262") (pin "1") (pinfunction "1_1") (pintype "passive"))
      (node (ref "TP6") (pin "1") (pinfunction "1_1") (pintype "passive"))
      (node (ref "U9") (pin "56") (pinfunction "PWRON_56") (pintype "input"))
    )
    (net (code "32") (name "/SW1CFB") (class "Default")
      (node (ref "R384") (pin "2") (pinfunction "2_2") (pintype "passive"))
      (node (ref "U9") (pin "13") (pinfunction "SW1CFB_13") (pintype "passive"))
    )
    (net (code "33") (name "/SW1CLX") (class "Default")
      (node (ref "L8") (pin "2") (pinfunction "2_2") (pintype "passive"))
      (node (ref "U9") (pin "11") (pinfunction "SW1CLX_11") (pintype "output"))
    )
    (net (code "34") (name "/SW1LX") (class "Default")
      (node (ref "L1") (pin "1") (pinfunction "1_1") (pintype "passive"))
      (node (ref "U9") (pin "8") (pinfunction "SW1ALX_8") (pintype "passive"))
      (node (ref "U9") (pin "9") (pinfunction "SW1BLX_9") (pintype "passive"))
    )
    (net (code "35") (name "/SW2LX") (class "Default")
      (node (ref "L10") (pin "1") (pinfunction "1_1") (pintype "passive"))
      (node (ref "U9") (pin "22") (pinfunction "SW2LX_22") (pintype "output"))
    )
    (net (code "36") (name "/SW3LX") (class "Default")
      (node (ref "L2") (pin "1") (pinfunction "1_1") (pintype "passive"))
      (node (ref "U9") (pin "35") (pinfunction "SW3BLX_35") (pintype "passive"))
      (node (ref "U9") (pin "36") (pinfunction "SW3ALX_36") (pintype "passive"))
    )
    (net (code "37") (name "/SW4LX") (class "Default")
      (node (ref "L9") (pin "1") (pinfunction "1_1") (pintype "passive"))
      (node (ref "U9") (pin "21") (pinfunction "SW4LX_21") (pintype "output"))
    )
    (net (code "38") (name "/SWBSTLX") (class "Default")
      (node (ref "D18") (pin "2") (pinfunction "Anode_2") (pintype "passive"))
      (node (ref "L11") (pin "2") (pinfunction "2_2") (pintype "passive"))
      (node (ref "U9") (pin "46") (pinfunction "SWBSTLX_46") (pintype "bidirectional"))
    )
    (net (code "39") (name "GND") (class "Default")
      (node (ref "C330") (pin "2") (pinfunction "2_2") (pintype "passive"))
      (node (ref "C331") (pin "2") (pinfunction "2_2") (pintype "passive"))
      (node (ref "C332") (pin "2") (pinfunction "2_2") (pintype "passive"))
      (node (ref "C333") (pin "2") (pinfunction "2_2") (pintype "passive"))
      (node (ref "C334") (pin "2") (pinfunction "2_2") (pintype "passive"))
      (node (ref "C335") (pin "2") (pinfunction "2_2") (pintype "passive"))
      (node (ref "C336") (pin "2") (pinfunction "2_2") (pintype "passive"))
      (node (ref "C337") (pin "2") (pinfunction "2_2") (pintype "passive"))
      (node (ref "C338") (pin "2") (pinfunction "2_2") (pintype "passive"))
      (node (ref "C339") (pin "2") (pinfunction "2_2") (pintype "passive"))
      (node (ref "C341") (pin "2") (pinfunction "2_2") (pintype "passive"))
      (node (ref "C342") (pin "2") (pinfunction "2_2") (pintype "passive"))
      (node (ref "C343") (pin "2") (pinfunction "2_2") (pintype "passive"))
      (node (ref "C344") (pin "2") (pinfunction "2_2") (pintype "passive"))
      (node (ref "C345") (pin "2") (pinfunction "2_2") (pintype "passive"))
      (node (ref "C346") (pin "2") (pinfunction "2_2") (pintype "passive"))
      (node (ref "C347") (pin "2") (pinfunction "2_2") (pintype "passive"))
      (node (ref "C348") (pin "2") (pinfunction "2_2") (pintype "passive"))
      (node (ref "C349") (pin "2") (pinfunction "2_2") (pintype "passive"))
      (node (ref "C350") (pin "2") (pinfunction "2_2") (pintype "passive"))
      (node (ref "C351") (pin "2") (pinfunction "2_2") (pintype "passive"))
      (node (ref "C352") (pin "2") (pinfunction "2_2") (pintype "passive"))
      (node (ref "C353") (pin "2") (pinfunction "2_2") (pintype "passive"))
      (node (ref "C354") (pin "2") (pinfunction "2_2") (pintype "passive"))
      (node (ref "C355") (pin "2") (pinfunction "2_2") (pintype "passive"))
      (node (ref "C356") (pin "2") (pinfunction "2_2") (pintype "passive"))
      (node (ref "C357") (pin "2") (pinfunction "2_2") (pintype "passive"))
      (node (ref "C358") (pin "2") (pinfunction "2_2") (pintype "passive"))
      (node (ref "C359") (pin "2") (pinfunction "2_2") (pintype "passive"))
      (node (ref "C360") (pin "2") (pinfunction "2_2") (pintype "passive"))
      (node (ref "C361") (pin "2") (pinfunction "2_2") (pintype "passive"))
      (node (ref "C362") (pin "2") (pinfunction "2_2") (pintype "passive"))
      (node (ref "C363") (pin "2") (pinfunction "2_2") (pintype "passive"))
      (node (ref "C364") (pin "2") (pinfunction "2_2") (pintype "passive"))
      (node (ref "C365") (pin "2") (pinfunction "2_2") (pintype "passive"))
      (node (ref "C366") (pin "2") (pinfunction "2_2") (pintype "passive"))
      (node (ref "C367") (pin "2") (pinfunction "2_2") (pintype "passive"))
      (node (ref "C368") (pin "2") (pinfunction "2_2") (pintype "passive"))
      (node (ref "C369") (pin "2") (pinfunction "2_2") (pintype "passive"))
      (node (ref "C370") (pin "2") (pinfunction "2_2") (pintype "passive"))
      (node (ref "C371") (pin "2") (pinfunction "2_2") (pintype "passive"))
      (node (ref "C372") (pin "2") (pinfunction "2_2") (pintype "passive"))
      (node (ref "C373") (pin "2") (pinfunction "2_2") (pintype "passive"))
      (node (ref "C374") (pin "2") (pinfunction "2_2") (pintype "passive"))
      (node (ref "C375") (pin "2") (pinfunction "2_2") (pintype "passive"))
      (node (ref "C376") (pin "2") (pinfunction "2_2") (pintype "passive"))
      (node (ref "C377") (pin "2") (pinfunction "2_2") (pintype "passive"))
      (node (ref "C378") (pin "2") (pinfunction "2_2") (pintype "passive"))
      (node (ref "C379") (pin "2") (pinfunction "2_2") (pintype "passive"))
      (node (ref "C380") (pin "2") (pinfunction "2_2") (pintype "passive"))
      (node (ref "C404") (pin "2") (pinfunction "2_2") (pintype "passive"))
      (node (ref "C424") (pin "2") (pinfunction "2_2") (pintype "passive"))
      (node (ref "C425") (pin "2") (pinfunction "2_2") (pintype "passive"))
      (node (ref "C426") (pin "2") (pinfunction "2_2") (pintype "passive"))
      (node (ref "C434") (pin "2") (pinfunction "2_2") (pintype "passive"))
      (node (ref "C435") (pin "2") (pinfunction "2_2") (pintype "passive"))
      (node (ref "C436") (pin "2") (pinfunction "2_2") (pintype "passive"))
      (node (ref "C437") (pin "2") (pinfunction "2_2") (pintype "passive"))
      (node (ref "R237") (pin "1") (pinfunction "1_1") (pintype "passive"))
      (node (ref "R265") (pin "1") (pinfunction "1_1") (pintype "passive"))
      (node (ref "U9") (pin "14") (pinfunction "SW1VSSSNS_14") (pintype "power_in"))
      (node (ref "U9") (pin "15") (pinfunction "GNDREF1_15") (pintype "power_in"))
      (node (ref "U9") (pin "32") (pinfunction "SW3VSSSNS_32") (pintype "power_in"))
      (node (ref "U9") (pin "48") (pinfunction "GNDREF_48") (pintype "power_in"))
      (node (ref "U9") (pin "5") (pinfunction "ICTEST_5") (pintype "input"))
      (node (ref "U9") (pin "57") (pinfunction "EPGND_57") (pintype "power_in"))
    )
    (net (code "40") (name "unconnected-(U9C-SW3BFB-Pad33)") (class "Default")
      (node (ref "U9") (pin "33") (pinfunction "SW3BFB_33") (pintype "input+no_connect"))
    )
  )
)
